# sun2usb.net
KiCad netlist of a schematic drawn in EAGLE
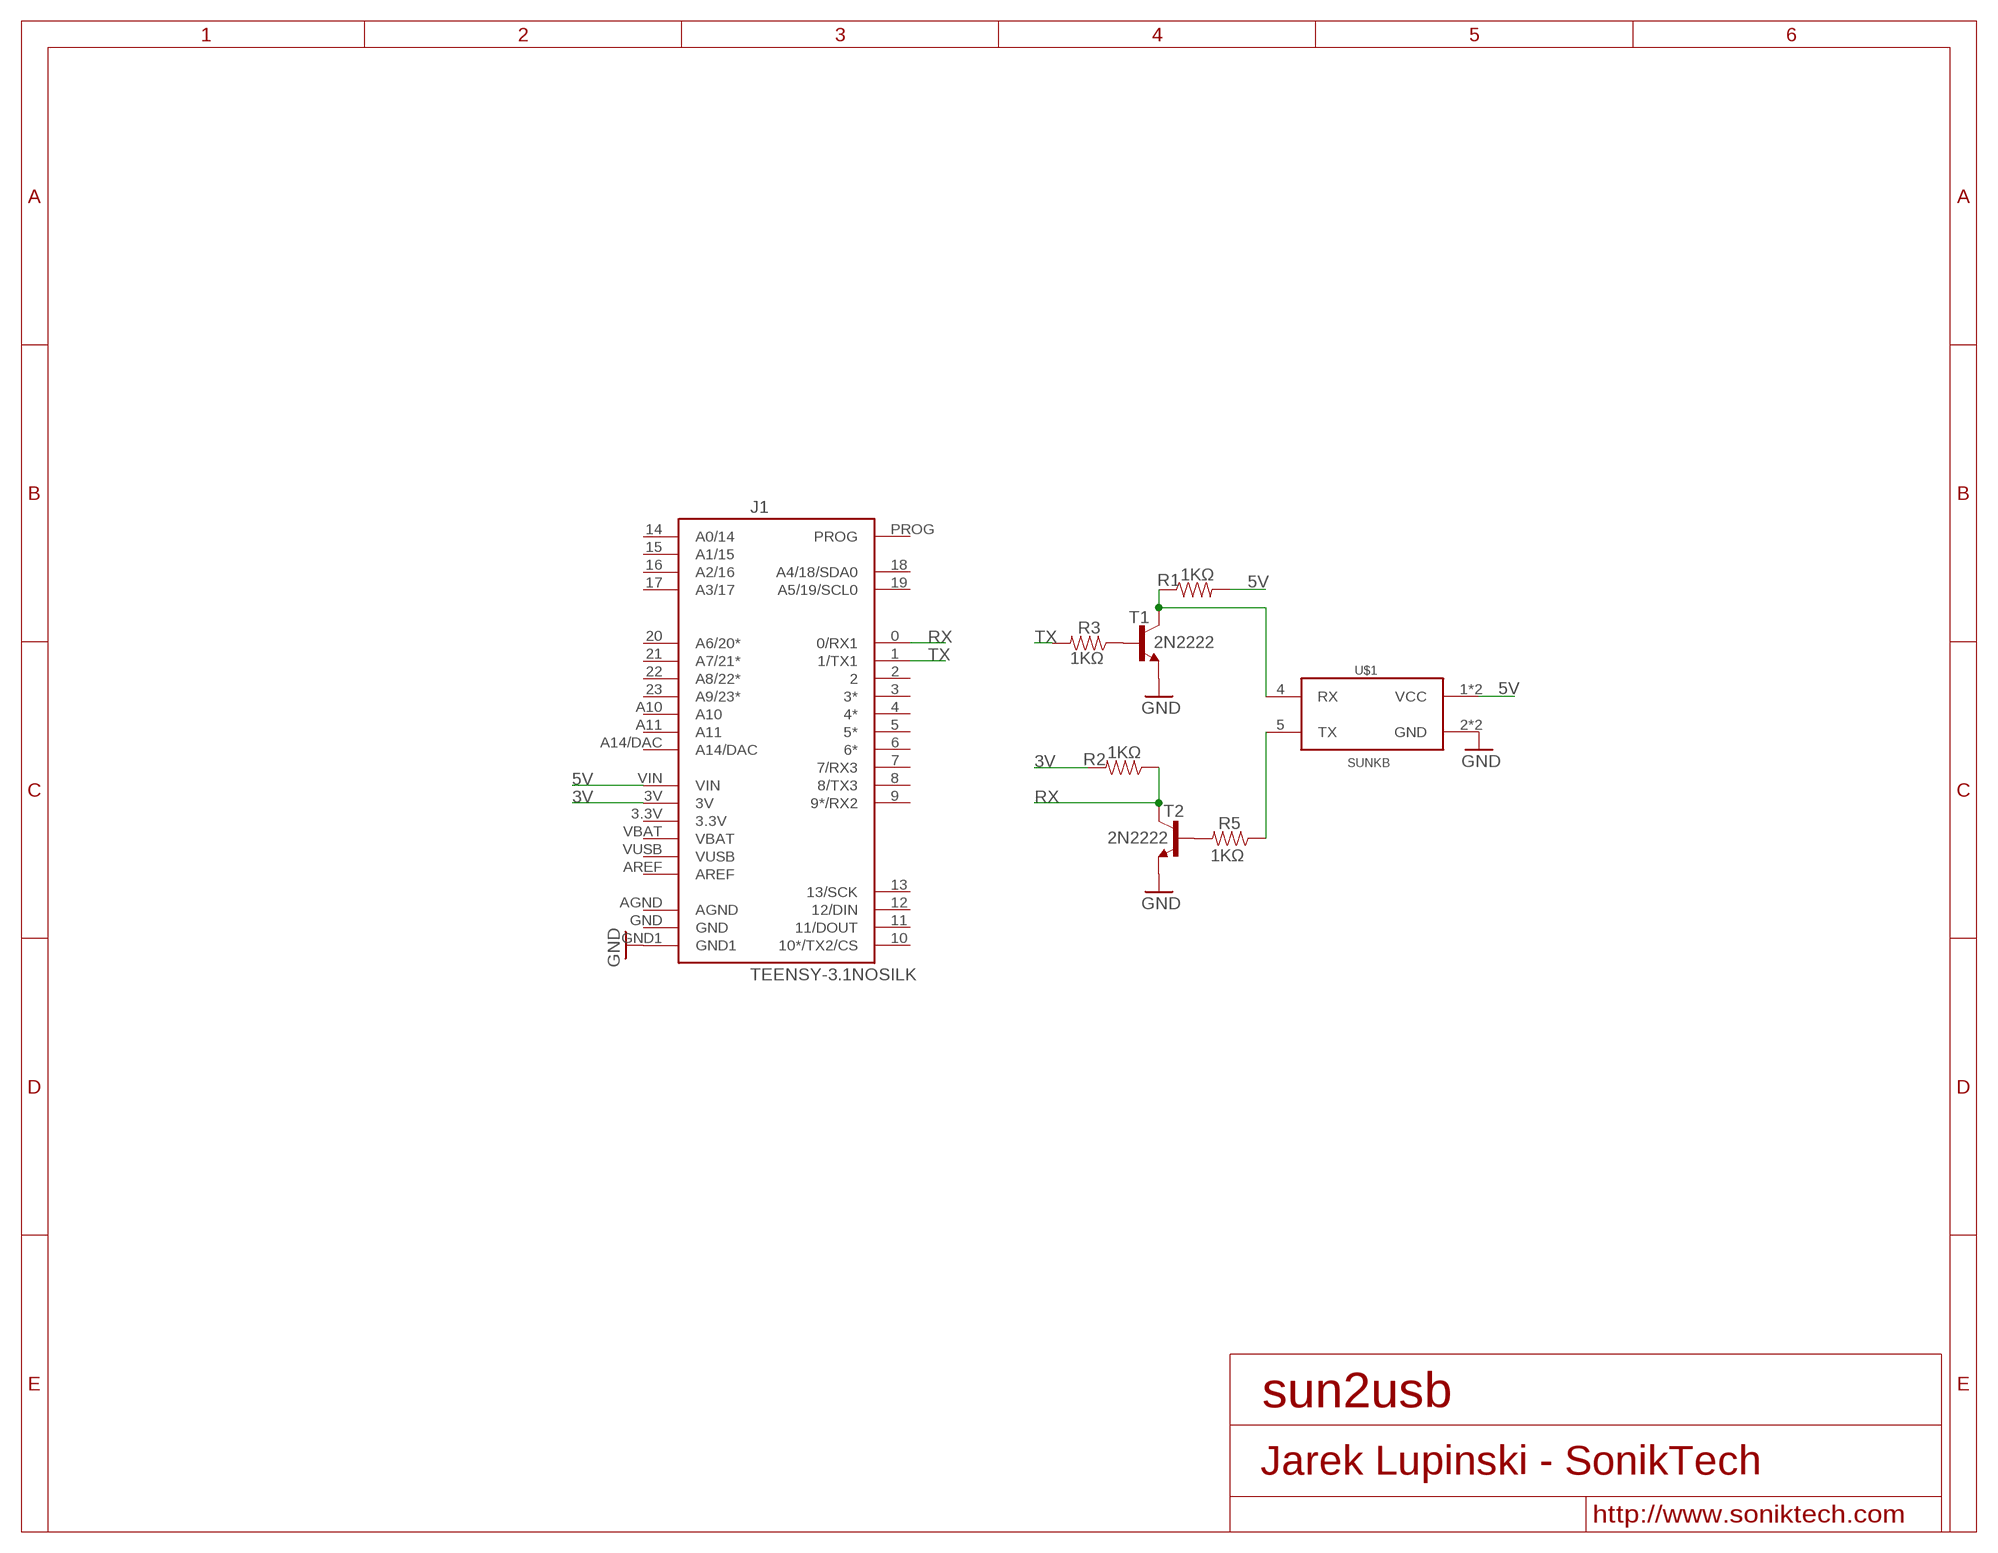
[diagram p0: schematic, sheet 1]

(export (version "E")
  (design (tool "Eeschema 10.0.6"))
  (components
    (comp (ref "J1")
      (value "TEENSY-3.1NOSILK")
      (footprint "eagle-import:TEENSY-3.1_NOSILK")
      (libsource (lib "eagle-import") (part "TEENSY-3.1NOSILK"))
    )
    (comp (ref "R1")
      (value "1KΩ")
      (footprint "eagle-import:AXIAL-0.4")
      (libsource (lib "eagle-import") (part "RESISTORPTH-1/4W"))
    )
    (comp (ref "R2")
      (value "1KΩ")
      (footprint "eagle-import:AXIAL-0.4")
      (libsource (lib "eagle-import") (part "RESISTORPTH-1/4W"))
    )
    (comp (ref "R3")
      (value "1KΩ")
      (footprint "eagle-import:AXIAL-0.4")
      (libsource (lib "eagle-import") (part "RESISTORPTH-1/4W"))
    )
    (comp (ref "R5")
      (value "1KΩ")
      (footprint "eagle-import:AXIAL-0.4")
      (libsource (lib "eagle-import") (part "RESISTORPTH-1/4W"))
    )
    (comp (ref "T1")
      (value "2N2222")
      (footprint "eagle-import:TO92-EBC-OVAL")
      (libsource (lib "eagle-import") (part "2N2222"))
    )
    (comp (ref "T2")
      (value "2N2222")
      (footprint "eagle-import:TO92-EBC-OVAL")
      (libsource (lib "eagle-import") (part "2N2222"))
    )
    (comp (ref "U$1")
      (value "SUNKB")
      (footprint "eagle-import:MINI8DIN")
      (libsource (lib "eagle-import") (part "SUNKB"))
    )
  )
  (nets
    (net (code "1") (name "/3V") (class "Default")
      (node (ref "J1") (pin "3V") (pinfunction "3V_3V") (pintype "bidirectional"))
      (node (ref "R2") (pin "P$2") (pinfunction "2_P$2") (pintype "passive"))
    )
    (net (code "2") (name "/5V") (class "Default")
      (node (ref "J1") (pin "VIN") (pinfunction "VIN_VIN") (pintype "bidirectional"))
      (node (ref "R1") (pin "P$2") (pinfunction "2_P$2") (pintype "passive"))
      (node (ref "U$1") (pin "1") (pinfunction "VCC_1") (pintype "bidirectional"))
      (node (ref "U$1") (pin "8") (pinfunction "VCC_8") (pintype "bidirectional"))
    )
    (net (code "3") (name "/RX") (class "Default")
      (node (ref "J1") (pin "0") (pinfunction "0/RX1_0") (pintype "bidirectional"))
      (node (ref "R2") (pin "P$1") (pinfunction "1_P$1") (pintype "passive"))
      (node (ref "T2") (pin "C") (pinfunction "C_C") (pintype "passive"))
    )
    (net (code "4") (name "/TX") (class "Default")
      (node (ref "J1") (pin "1") (pinfunction "1/TX1_1") (pintype "bidirectional"))
      (node (ref "R3") (pin "P$2") (pinfunction "2_P$2") (pintype "passive"))
    )
    (net (code "5") (name "GND") (class "Default")
      (node (ref "J1") (pin "GND1") (pinfunction "GND1_GND1") (pintype "bidirectional"))
      (node (ref "T1") (pin "E") (pinfunction "E_E") (pintype "passive"))
      (node (ref "T2") (pin "E") (pinfunction "E_E") (pintype "passive"))
      (node (ref "U$1") (pin "2") (pinfunction "GND_2") (pintype "bidirectional"))
      (node (ref "U$1") (pin "3") (pinfunction "GND_3") (pintype "bidirectional"))
    )
    (net (code "6") (name "Net-(R1-1)") (class "Default")
      (node (ref "R1") (pin "P$1") (pinfunction "1_P$1") (pintype "passive"))
      (node (ref "T1") (pin "C") (pinfunction "C_C") (pintype "passive"))
      (node (ref "U$1") (pin "4") (pinfunction "RX_4") (pintype "bidirectional"))
    )
    (net (code "7") (name "Net-(R3-1)") (class "Default")
      (node (ref "R3") (pin "P$1") (pinfunction "1_P$1") (pintype "passive"))
      (node (ref "T1") (pin "B") (pinfunction "B_B") (pintype "passive"))
    )
    (net (code "8") (name "Net-(R5-1)") (class "Default")
      (node (ref "R5") (pin "P$1") (pinfunction "1_P$1") (pintype "passive"))
      (node (ref "U$1") (pin "5") (pinfunction "TX_5") (pintype "bidirectional"))
    )
    (net (code "9") (name "Net-(R5-2)") (class "Default")
      (node (ref "R5") (pin "P$2") (pinfunction "2_P$2") (pintype "passive"))
      (node (ref "T2") (pin "B") (pinfunction "B_B") (pintype "passive"))
    )
    (net (code "10") (name "unconnected-(J1-3*-Pad3)") (class "Default")
      (node (ref "J1") (pin "3") (pinfunction "3*_3") (pintype "bidirectional"))
    )
    (net (code "11") (name "unconnected-(J1-4*-Pad4)") (class "Default")
      (node (ref "J1") (pin "4") (pinfunction "4*_4") (pintype "bidirectional"))
    )
    (net (code "12") (name "unconnected-(J1-5*-Pad5)") (class "Default")
      (node (ref "J1") (pin "5") (pinfunction "5*_5") (pintype "bidirectional"))
    )
    (net (code "13") (name "unconnected-(J1-6*-Pad6)") (class "Default")
      (node (ref "J1") (pin "6") (pinfunction "6*_6") (pintype "bidirectional"))
    )
    (net (code "14") (name "unconnected-(J1-7{slash}RX3-Pad7)") (class "Default")
      (node (ref "J1") (pin "7") (pinfunction "7/RX3_7") (pintype "bidirectional"))
    )
    (net (code "15") (name "unconnected-(J1-8{slash}TX3-Pad8)") (class "Default")
      (node (ref "J1") (pin "8") (pinfunction "8/TX3_8") (pintype "bidirectional"))
    )
    (net (code "16") (name "unconnected-(J1-9*{slash}RX2-Pad9)") (class "Default")
      (node (ref "J1") (pin "9") (pinfunction "9*/RX2_9") (pintype "bidirectional"))
    )
    (net (code "17") (name "unconnected-(J1-10*{slash}TX2{slash}CS-Pad10)") (class "Default")
      (node (ref "J1") (pin "10") (pinfunction "10*/TX2/CS_10") (pintype "bidirectional"))
    )
    (net (code "18") (name "unconnected-(J1-11{slash}DOUT-Pad11)") (class "Default")
      (node (ref "J1") (pin "11") (pinfunction "11/DOUT_11") (pintype "bidirectional"))
    )
    (net (code "19") (name "unconnected-(J1-12{slash}DIN-Pad12)") (class "Default")
      (node (ref "J1") (pin "12") (pinfunction "12/DIN_12") (pintype "bidirectional"))
    )
    (net (code "20") (name "unconnected-(J1-13{slash}SCK-Pad13)") (class "Default")
      (node (ref "J1") (pin "13") (pinfunction "13/SCK_13") (pintype "bidirectional"))
    )
    (net (code "21") (name "unconnected-(J1-A0{slash}14-Pad14)") (class "Default")
      (node (ref "J1") (pin "14") (pinfunction "A0/14_14") (pintype "bidirectional"))
    )
    (net (code "22") (name "unconnected-(J1-A1{slash}15-Pad15)") (class "Default")
      (node (ref "J1") (pin "15") (pinfunction "A1/15_15") (pintype "bidirectional"))
    )
    (net (code "23") (name "unconnected-(J1-A2{slash}16-Pad16)") (class "Default")
      (node (ref "J1") (pin "16") (pinfunction "A2/16_16") (pintype "bidirectional"))
    )
    (net (code "24") (name "unconnected-(J1-A3{slash}17-Pad17)") (class "Default")
      (node (ref "J1") (pin "17") (pinfunction "A3/17_17") (pintype "bidirectional"))
    )
    (net (code "25") (name "unconnected-(J1-A4{slash}18{slash}SDA0-Pad18)") (class "Default")
      (node (ref "J1") (pin "18") (pinfunction "A4/18/SDA0_18") (pintype "bidirectional"))
    )
    (net (code "26") (name "unconnected-(J1-A5{slash}19{slash}SCL0-Pad19)") (class "Default")
      (node (ref "J1") (pin "19") (pinfunction "A5/19/SCL0_19") (pintype "bidirectional"))
    )
    (net (code "27") (name "unconnected-(J1-A6{slash}20*-Pad20)") (class "Default")
      (node (ref "J1") (pin "20") (pinfunction "A6/20*_20") (pintype "bidirectional"))
    )
    (net (code "28") (name "unconnected-(J1-A7{slash}21*-Pad21)") (class "Default")
      (node (ref "J1") (pin "21") (pinfunction "A7/21*_21") (pintype "bidirectional"))
    )
    (net (code "29") (name "unconnected-(J1-A8{slash}22*-Pad22)") (class "Default")
      (node (ref "J1") (pin "22") (pinfunction "A8/22*_22") (pintype "bidirectional"))
    )
    (net (code "30") (name "unconnected-(J1-A9{slash}23*-Pad23)") (class "Default")
      (node (ref "J1") (pin "23") (pinfunction "A9/23*_23") (pintype "bidirectional"))
    )
    (net (code "31") (name "unconnected-(J1-Pad2)") (class "Default")
      (node (ref "J1") (pin "2") (pinfunction "2_2") (pintype "bidirectional"))
    )
    (net (code "32") (name "unconnected-(J1-Pad3.3V)") (class "Default")
      (node (ref "J1") (pin "3.3V") (pinfunction "3.3V_3.3V") (pintype "bidirectional"))
    )
    (net (code "33") (name "unconnected-(J1-PadA10)") (class "Default")
      (node (ref "J1") (pin "A10") (pinfunction "A10_A10") (pintype "bidirectional"))
    )
    (net (code "34") (name "unconnected-(J1-PadA11)") (class "Default")
      (node (ref "J1") (pin "A11") (pinfunction "A11_A11") (pintype "bidirectional"))
    )
    (net (code "35") (name "unconnected-(J1-PadA14{slash}DAC)") (class "Default")
      (node (ref "J1") (pin "A14/DAC") (pinfunction "A14/DAC_A14/DAC") (pintype "bidirectional"))
    )
    (net (code "36") (name "unconnected-(J1-PadAGND)") (class "Default")
      (node (ref "J1") (pin "AGND") (pinfunction "AGND_AGND") (pintype "bidirectional"))
    )
    (net (code "37") (name "unconnected-(J1-PadAREF)") (class "Default")
      (node (ref "J1") (pin "AREF") (pinfunction "AREF_AREF") (pintype "bidirectional"))
    )
    (net (code "38") (name "unconnected-(J1-PadGND)") (class "Default")
      (node (ref "J1") (pin "GND") (pinfunction "GND_GND") (pintype "bidirectional"))
    )
    (net (code "39") (name "unconnected-(J1-PadPROG)") (class "Default")
      (node (ref "J1") (pin "PROG") (pinfunction "PROG_PROG") (pintype "bidirectional"))
    )
    (net (code "40") (name "unconnected-(J1-PadVBAT)") (class "Default")
      (node (ref "J1") (pin "VBAT") (pinfunction "VBAT_VBAT") (pintype "bidirectional"))
    )
    (net (code "41") (name "unconnected-(J1-PadVUSB)") (class "Default")
      (node (ref "J1") (pin "VUSB") (pinfunction "VUSB_VUSB") (pintype "bidirectional"))
    )
  )
)
